# Power_supply.net
KiCad netlist of a schematic drawn in Altium Designer
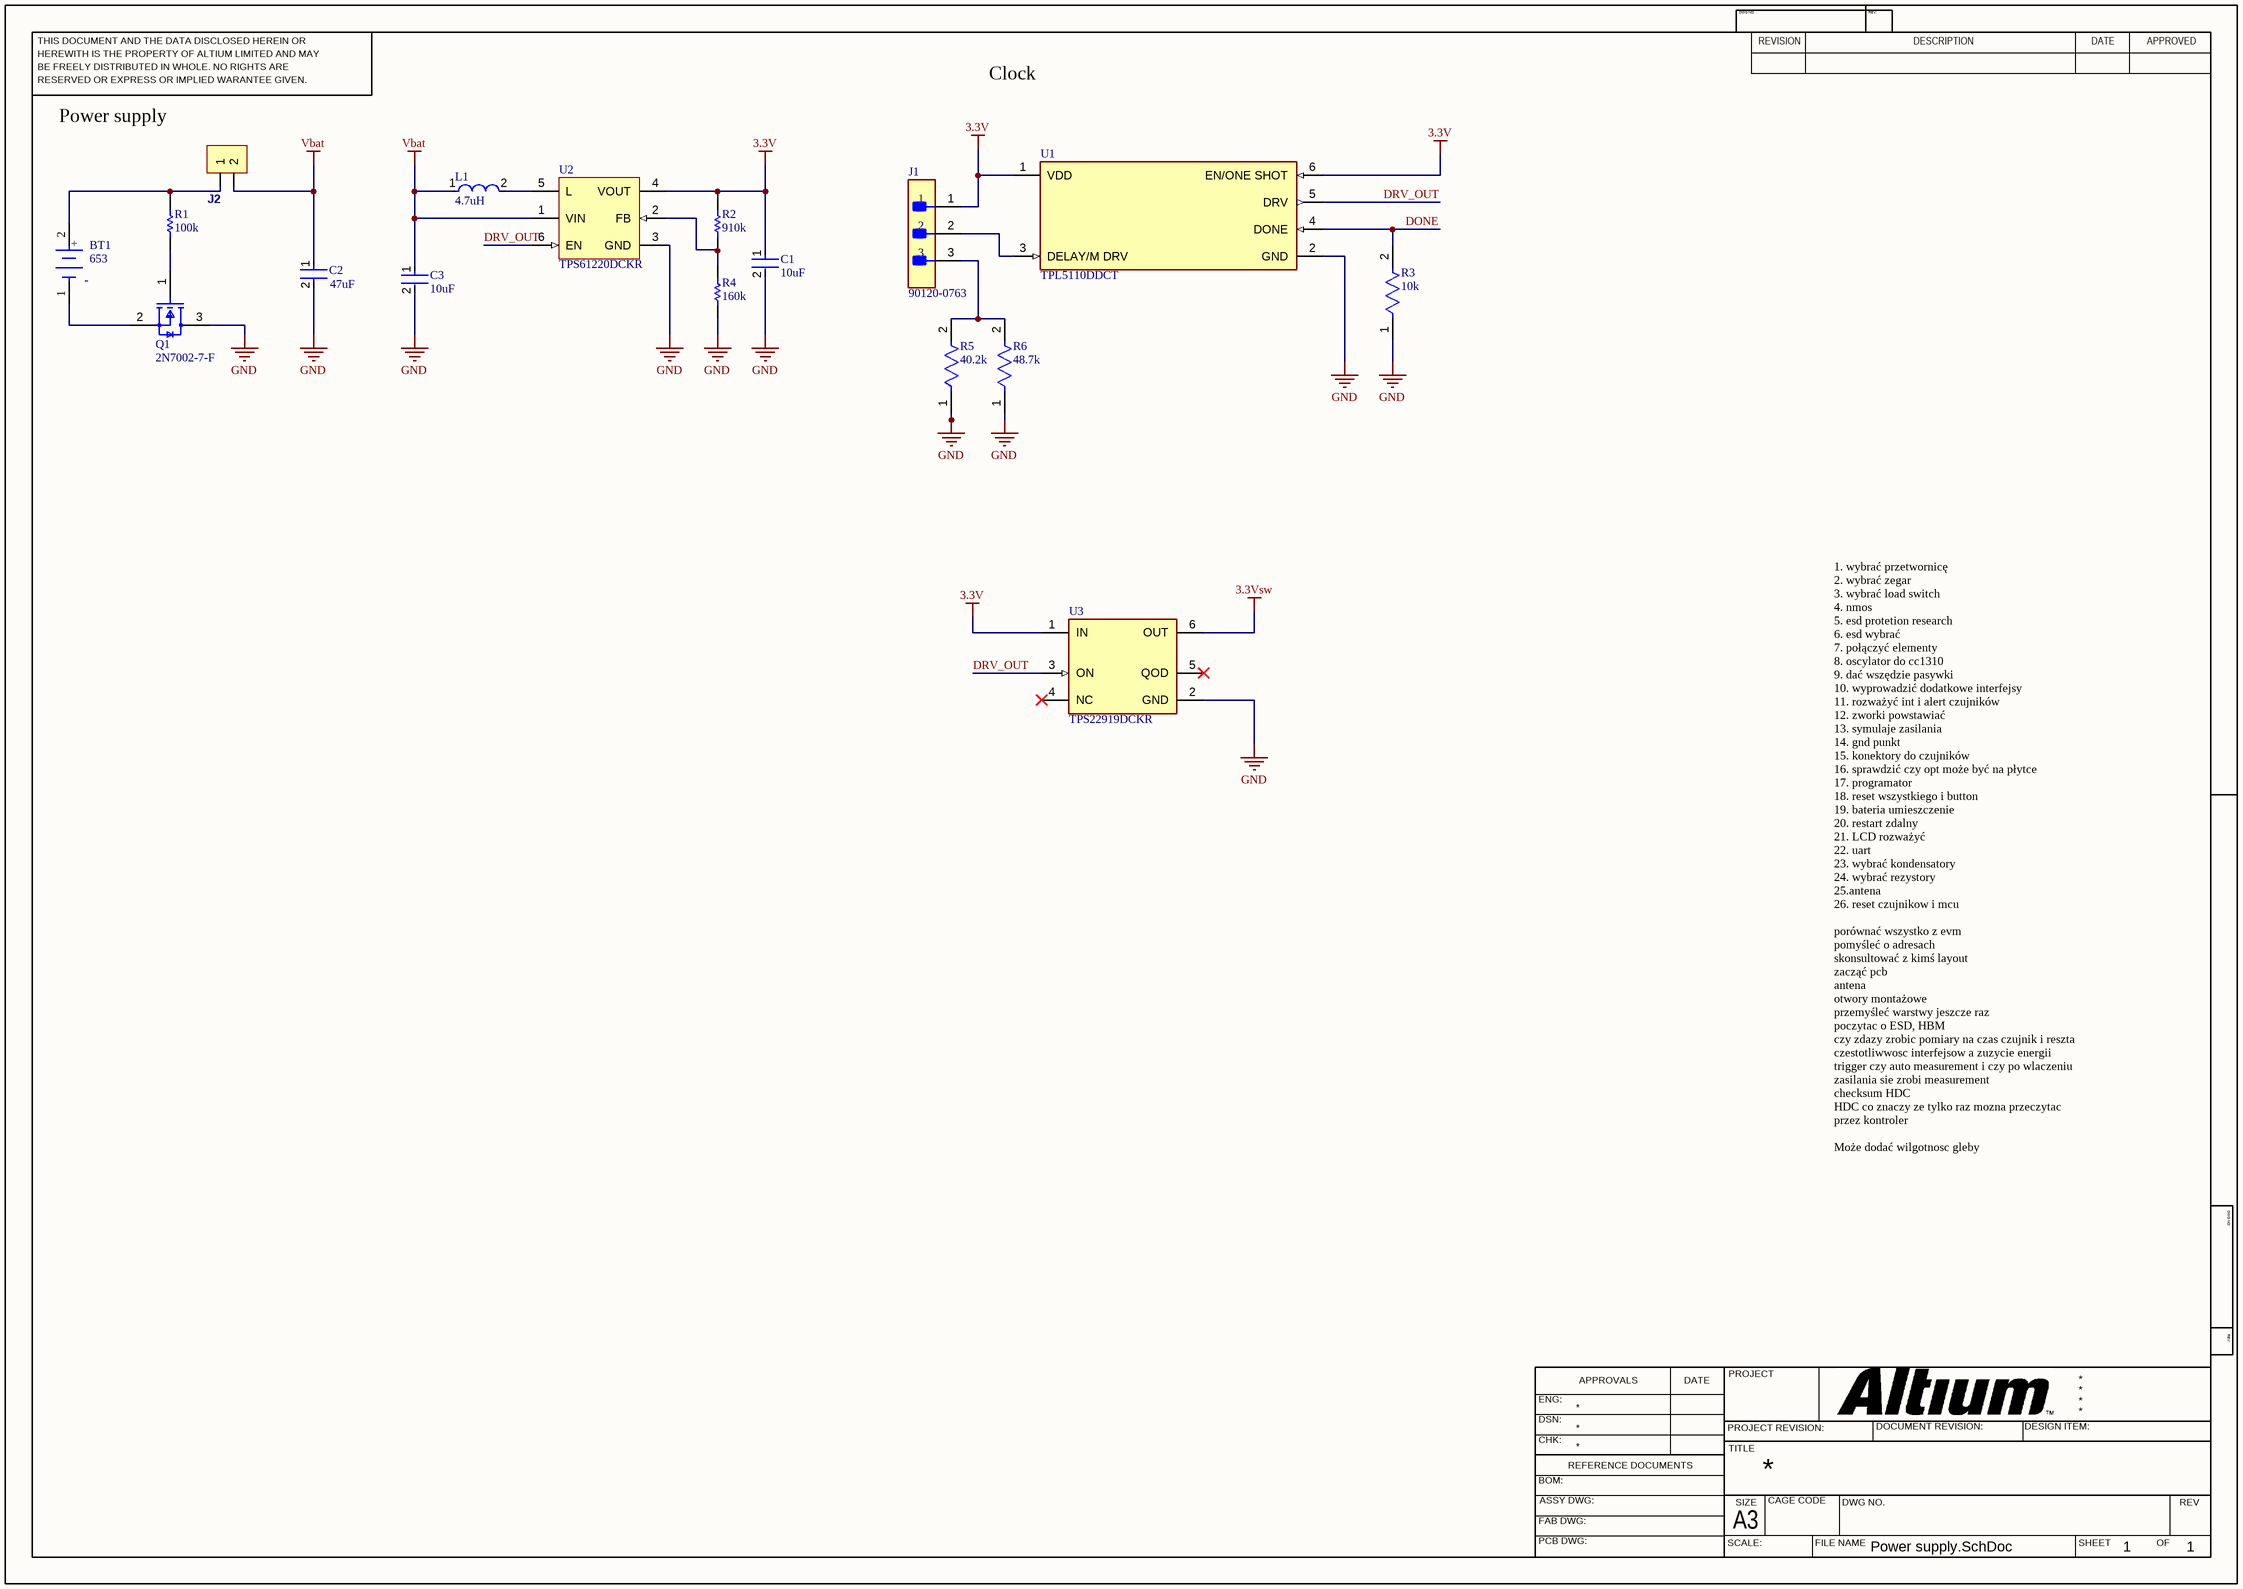
[diagram p0: Power supply.SchDoc]

(export (version "E")
  (design (tool "Eeschema 10.0.6"))
  (components
    (comp (ref "BT1")
      (value "653")
      (footprint "FP-653-MFG")
      (description "Adafruit Accessories Sewable CR2032 Battery Holder")
      (libsource (lib "Altium Content Vault") (part "60d3b5b901a8747834971d0eb8cf3fd"))
    )
    (comp (ref "C1")
      (value "10uF")
      (footprint "FP-GRM188-0_2-MFG")
      (fields (field (name "TOLERANCE") "10%"))
      (libsource (lib "Altium Content Vault") (part "11868f565c42a9108669ba33697ecf6"))
    )
    (comp (ref "C2")
      (value "47uF")
      (footprint "FP-GRM31C-0_2-e0_3_0_8-IPC_C")
      (fields (field (name "TOLERANCE") "20%") (field (name "VOLTAGE") "10V"))
      (libsource (lib "Altium Content Vault") (part "02cd4be3c70576c341d710602a673aa"))
    )
    (comp (ref "C3")
      (value "10uF")
      (footprint "FP-1210-L_3_3_0_4-W_2_5_0-IPC_A")
      (description "1210ZC106KAT2A CAP CER 10UF 10V X7R 1210")
      (fields (field (name "VOLTAGE") "10V") (field (name "TOLERANCE") "10%"))
      (libsource (lib "Altium Content Vault") (part "b4654b650e69147ec39a6b967a45e02"))
    )
    (comp (ref "J1")
      (value "90120-0763")
      (footprint "FP-90120-0763-MFG")
      (description "CONN HEADER VERT 3POS 2.54MM")
      (fields
        (field (name "MANUFACTURER") "Molex")
        (field (name "OCTOPART") "https://octopart.com/90120-0763-molex-655433")
      )
      (libsource (lib "Altium Content Vault") (part "0d3f023dd272f625e17a2be33dea85f"))
    )
    (comp (ref "J2")
      (value "CN_2x1")
      (footprint "GP_2x1")
      (fields (field (name "SOURCE") "goldpin_male_sch.SchLib"))
      (libsource (lib "MyWorkspace") (part "CN_2x1"))
    )
    (comp (ref "L1")
      (value "4.7uH")
      (footprint "FP-LQH3NPH_ME-MFG")
      (fields (field (name "TOLERANCE") "20%"))
      (libsource (lib "Altium Content Vault") (part "725321dda6339637d4d059423bc1c3c"))
    )
    (comp (ref "Q1")
      (value "2N7002-7-F")
      (footprint "FP-SOT23-MFG")
      (description "MOSFET N-CH 60V 115MA SOT23-3")
      (fields (field (name "VOLTAGE") "60V"))
      (libsource (lib "Altium Content Vault") (part "3b9c635fedb024a5347a57b145af9cc"))
    )
    (comp (ref "R1")
      (value "100k")
      (footprint "RESC0603(1608)_N")
      (description "100K 0.1W 1% 0603 (1608 Metric)  SMD")
      (fields (field (name "POWER") "0.1 W") (field (name "TOLERANCE") "1 %"))
      (libsource (lib "Altium Content Vault") (part "RES"))
    )
    (comp (ref "R2")
      (value "910k")
      (footprint "RESC3226X70X40NL20T20")
      (description "RK73B2ETTD914J")
      (fields (field (name "MANUFACTURER") "KOA Speer"))
      (libsource (lib "Altium Content Vault") (part "RES"))
    )
    (comp (ref "R3")
      (value "10k")
      (footprint "FP-RK73HW3A-IPC_A")
      (description "RK73HW3ATTE1002F 10kΩ ±1% 1W Chip Resistor 2512 Thick Film AEC-Q200 Qualified")
      (fields (field (name "TOLERANCE") "1%"))
      (libsource (lib "Altium Content Vault") (part "1029c3af85768c4190bb7ad29bc67b5"))
    )
    (comp (ref "R4")
      (value "160k")
      (footprint "RESC3225X60X45LL20T20")
      (description "CRCW1210160KJNEA")
      (fields (field (name "MANUFACTURER") "Vishay Dale"))
      (libsource (lib "Altium Content Vault") (part "RES"))
    )
    (comp (ref "R5")
      (value "40.2k")
      (footprint "FP-MCT0603-IPC_A")
      (description "MCT06030C4029FP500 RES SMD 100 OHM 1% 1/8W 0603")
      (fields (field (name "TOLERANCE") "1%"))
      (libsource (lib "Altium Content Vault") (part "1029c3af85768c4190bb7ad29bc67b5"))
    )
    (comp (ref "R6")
      (value "48.7k")
      (footprint "FP-MCT0603-IPC_A")
      (description "MCT06030C4029FP500 RES SMD 100 OHM 1% 1/8W 0603")
      (fields (field (name "TOLERANCE") "1%"))
      (libsource (lib "Altium Content Vault") (part "1029c3af85768c4190bb7ad29bc67b5"))
    )
    (comp (ref "U1")
      (value "TPL5110DDCT")
      (footprint "FP-DDC0006A-MFG")
      (description "IC OSC PROG TIMER TSOT23-6")
      (fields
        (field (name "OCTOPART") "https://octopart.com/tpl5110ddct-texas+instruments-52670271")
        (field (name "MANUFACTURER") "Texas Instruments")
      )
      (libsource (lib "Altium Content Vault") (part "6ed543a5282c23458c04814cca5b1ac"))
    )
    (comp (ref "U2")
      (value "TPS61220DCKR")
      (footprint "DCK0006A_L")
      (fields (field (name "MANUFACTURER") "Texas Instruments"))
      (libsource (lib "Altium Content Vault") (part "TI-TPS61220DCK6"))
    )
    (comp (ref "U3")
      (value "TPS22919DCKR")
      (footprint "FP-DCK0006A-MFG")
      (description "POWER MANAGEMENT")
      (libsource (lib "Altium Content Vault") (part "7dede5ae6ec4f64f362f8612ed9bb45"))
    )
  )
  (nets
    (net (code "1") (name "/DONE") (class "Default")
      (node (ref "R3") (pin "2") (pinfunction "2_2") (pintype "passive"))
      (node (ref "U1") (pin "4") (pinfunction "DONE_4") (pintype "input"))
    )
    (net (code "2") (name "/DRV_OUT") (class "Default")
      (node (ref "U1") (pin "5") (pinfunction "DRV_5") (pintype "output"))
      (node (ref "U2") (pin "6") (pinfunction "EN_6") (pintype "input"))
      (node (ref "U3") (pin "3") (pinfunction "ON_3") (pintype "input"))
    )
    (net (code "3") (name "3.3V") (class "Default")
      (node (ref "C1") (pin "1") (pinfunction "1_1") (pintype "passive"))
      (node (ref "J1") (pin "1") (pinfunction "1_1") (pintype "passive"))
      (node (ref "R2") (pin "2") (pinfunction "2_2") (pintype "passive"))
      (node (ref "U1") (pin "1") (pinfunction "VDD_1") (pintype "power_in"))
      (node (ref "U1") (pin "6") (pinfunction "EN/ONE_SHOT_6") (pintype "input"))
      (node (ref "U2") (pin "4") (pinfunction "VOUT_4") (pintype "power_in"))
      (node (ref "U3") (pin "1") (pinfunction "IN_1") (pintype "power_in"))
    )
    (net (code "4") (name "3.3Vsw") (class "Default")
      (node (ref "U3") (pin "6") (pinfunction "OUT_6") (pintype "power_in"))
    )
    (net (code "5") (name "GND") (class "Default")
      (node (ref "C1") (pin "2") (pinfunction "2_2") (pintype "passive"))
      (node (ref "C2") (pin "2") (pinfunction "2_2") (pintype "passive"))
      (node (ref "C3") (pin "2") (pinfunction "2_2") (pintype "passive"))
      (node (ref "Q1") (pin "3") (pinfunction "D_3") (pintype "passive"))
      (node (ref "R3") (pin "1") (pinfunction "1_1") (pintype "passive"))
      (node (ref "R4") (pin "1") (pinfunction "1_1") (pintype "passive"))
      (node (ref "R5") (pin "1") (pinfunction "1_1") (pintype "passive"))
      (node (ref "R6") (pin "1") (pinfunction "1_1") (pintype "passive"))
      (node (ref "U1") (pin "2") (pinfunction "GND_2") (pintype "power_in"))
      (node (ref "U2") (pin "3") (pinfunction "GND_3") (pintype "power_in"))
      (node (ref "U3") (pin "2") (pinfunction "GND_2") (pintype "power_in"))
    )
    (net (code "6") (name "Net-(BT1-A)") (class "Default")
      (node (ref "BT1") (pin "2") (pinfunction "A_2") (pintype "passive"))
      (node (ref "J2") (pin "1") (pinfunction "1_1") (pintype "passive"))
      (node (ref "R1") (pin "2") (pinfunction "2_2") (pintype "passive"))
    )
    (net (code "7") (name "Net-(BT1-C)") (class "Default")
      (node (ref "BT1") (pin "1") (pinfunction "C_1") (pintype "passive"))
      (node (ref "Q1") (pin "2") (pinfunction "S_2") (pintype "passive"))
    )
    (net (code "8") (name "Net-(J1-Pad3)") (class "Default")
      (node (ref "J1") (pin "3") (pinfunction "3_3") (pintype "passive"))
      (node (ref "R5") (pin "2") (pinfunction "2_2") (pintype "passive"))
      (node (ref "R6") (pin "2") (pinfunction "2_2") (pintype "passive"))
    )
    (net (code "9") (name "Net-(Q1-G)") (class "Default")
      (node (ref "Q1") (pin "1") (pinfunction "G_1") (pintype "passive"))
      (node (ref "R1") (pin "1") (pinfunction "1_1") (pintype "passive"))
    )
    (net (code "10") (name "Net-(U1-DELAY{slash}M_DRV)") (class "Default")
      (node (ref "J1") (pin "2") (pinfunction "2_2") (pintype "passive"))
      (node (ref "U1") (pin "3") (pinfunction "DELAY/M_DRV_3") (pintype "input"))
    )
    (net (code "11") (name "Net-(U2-FB)") (class "Default")
      (node (ref "R2") (pin "1") (pinfunction "1_1") (pintype "passive"))
      (node (ref "R4") (pin "2") (pinfunction "2_2") (pintype "passive"))
      (node (ref "U2") (pin "2") (pinfunction "FB_2") (pintype "input"))
    )
    (net (code "12") (name "Net-(U2-L)") (class "Default")
      (node (ref "L1") (pin "2") (pinfunction "2_2") (pintype "passive"))
      (node (ref "U2") (pin "5") (pinfunction "L_5") (pintype "power_in"))
    )
    (net (code "13") (name "Vbat") (class "Default")
      (node (ref "C2") (pin "1") (pinfunction "1_1") (pintype "passive"))
      (node (ref "C3") (pin "1") (pinfunction "1_1") (pintype "passive"))
      (node (ref "J2") (pin "2") (pinfunction "2_2") (pintype "passive"))
      (node (ref "L1") (pin "1") (pinfunction "1_1") (pintype "passive"))
      (node (ref "U2") (pin "1") (pinfunction "VIN_1") (pintype "power_in"))
    )
    (net (code "14") (name "unconnected-(U3-NC-Pad4)") (class "Default")
      (node (ref "U3") (pin "4") (pinfunction "NC_4") (pintype "passive+no_connect"))
    )
    (net (code "15") (name "unconnected-(U3-QOD-Pad5)") (class "Default")
      (node (ref "U3") (pin "5") (pinfunction "QOD_5") (pintype "passive+no_connect"))
    )
  )
)
